# PP5_Boot.net
KiCad netlist of a schematic drawn in Altium Designer
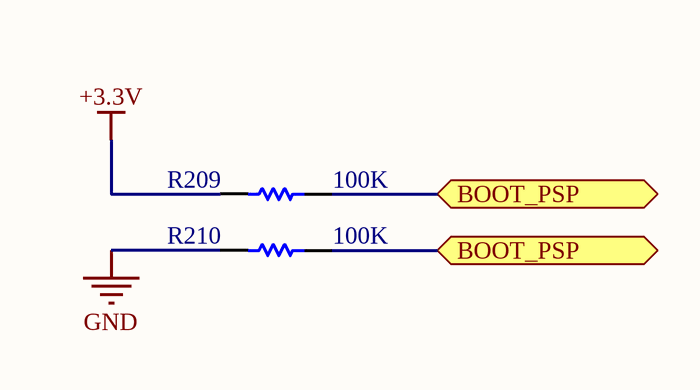
[diagram p0: PP5_Boot.SchDoc]

(export (version "E")
  (design (tool "Eeschema 10.0.6"))
  (components
    (comp (ref "R209")
      (value "100K")
      (footprint "AXIAL-0.3")
      (description "Resistor")
      (fields (field (name "Comment") "Res1"))
      (libsource (lib "Miscellaneous Devices") (part "Res1"))
    )
    (comp (ref "R210")
      (value "100K")
      (footprint "AXIAL-0.3")
      (description "Resistor")
      (fields (field (name "Comment") "Res1"))
      (libsource (lib "Miscellaneous Devices") (part "Res1"))
    )
  )
  (nets
    (net (code "1") (name "+3.3V") (class "Default")
      (node (ref "R209") (pin "2") (pinfunction "2_2") (pintype "passive"))
    )
    (net (code "2") (name "/BOOT_PSP") (class "Default")
      (node (ref "R209") (pin "1") (pinfunction "1_1") (pintype "passive"))
      (node (ref "R210") (pin "1") (pinfunction "1_1") (pintype "passive"))
    )
    (net (code "3") (name "GND") (class "Default")
      (node (ref "R210") (pin "2") (pinfunction "2_2") (pintype "passive"))
    )
  )
)
